# PhaseDriver.net
KiCad netlist of a schematic drawn in Altium Designer
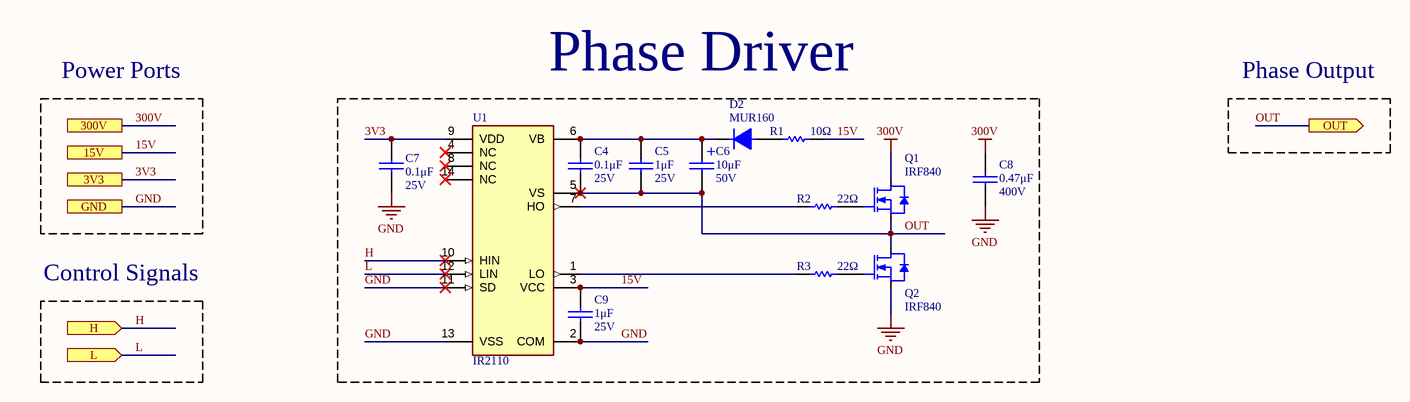
[diagram p0: PhaseDriver.SchDoc]

(export (version "E")
  (design (tool "Eeschema 10.0.6"))
  (components
    (comp (ref "C4")
      (value "0.1μF")
      (footprint "0805")
      (description "CAPACITOR")
      (fields (field (name "VOLTAGE RATING") "25V") (field (name "Comment") "CAP"))
      (libsource (lib "Inverter") (part "CAPACITOR"))
    )
    (comp (ref "C5")
      (value "1μF")
      (footprint "CAP100")
      (description "CAPACITOR")
      (fields (field (name "VOLTAGE RATING") "25V") (field (name "Comment") "CAP"))
      (libsource (lib "Inverter") (part "CAPACITOR"))
    )
    (comp (ref "C6")
      (value "10μF")
      (footprint "CAP100RP")
      (description "CAPACITOR POLARIZADO")
      (fields (field (name "VOLTAGE RATING") "50V") (field (name "Comment") "CAPPOL"))
      (libsource (lib "Inverter") (part "CAPACITOR POLARIZADO"))
    )
    (comp (ref "C7")
      (value "0.1μF")
      (footprint "0805")
      (description "CAPACITOR")
      (fields (field (name "VOLTAGE RATING") "25V") (field (name "Comment") "CAP"))
      (libsource (lib "Inverter") (part "CAPACITOR"))
    )
    (comp (ref "C8")
      (value "0.47μF")
      (footprint "CAP600")
      (description "CAPACITOR")
      (fields (field (name "VOLTAGE RATING") "400V") (field (name "Comment") "CAP"))
      (libsource (lib "Inverter") (part "CAPACITOR"))
    )
    (comp (ref "C9")
      (value "1μF")
      (footprint "CAP100")
      (description "CAPACITOR")
      (fields (field (name "VOLTAGE RATING") "25V") (field (name "Comment") "CAP"))
      (libsource (lib "Inverter") (part "CAPACITOR"))
    )
    (comp (ref "D2")
      (value "MUR160")
      (footprint "DO41")
      (fields (field (name "MANUFACTURER PART NUMBER") "MUR160"))
      (libsource (lib "Inverter") (part "MUR160"))
    )
    (comp (ref "Q1")
      (value "IRF840")
      (footprint "TO-220 V")
      (fields (field (name "MANUFACTURER") "Vishay") (field (name "MANUFACTURER PART NUMBER") "IRF840"))
      (libsource (lib "Inverter") (part "IRF840"))
    )
    (comp (ref "Q2")
      (value "IRF840")
      (footprint "TO-220 V")
      (fields (field (name "MANUFACTURER") "Vishay") (field (name "MANUFACTURER PART NUMBER") "IRF840"))
      (libsource (lib "Inverter") (part "IRF840"))
    )
    (comp (ref "R1")
      (value "10Ω")
      (footprint "0805")
      (description "RESISTOR")
      (fields (field (name "POWER") "1/10W") (field (name "Comment") "RES"))
      (libsource (lib "Inverter") (part "RESISTOR"))
    )
    (comp (ref "R2")
      (value "22Ω")
      (footprint "0805")
      (description "RESISTOR")
      (fields (field (name "POWER") "1/10W") (field (name "Comment") "RES"))
      (libsource (lib "Inverter") (part "RESISTOR"))
    )
    (comp (ref "R3")
      (value "22Ω")
      (footprint "0805")
      (description "RESISTOR")
      (fields (field (name "POWER") "1/10W") (field (name "Comment") "RES"))
      (libsource (lib "Inverter") (part "RESISTOR"))
    )
    (comp (ref "U1")
      (value "IR2110")
      (footprint "IR2110")
      (description "High and Low Side Driver")
      (fields
        (field (name "MANUFACTURER") "Infineon Technologies")
        (field (name "MANUFACTURER ORDER NUMBER") "IR2110")
      )
      (libsource (lib "Inverter") (part "IR2110"))
    )
  )
  (nets
    (net (code "1") (name "/3V3") (class "Default")
      (node (ref "C7") (pin "1") (pinfunction "1_1") (pintype "passive"))
      (node (ref "U1") (pin "9") (pinfunction "VDD_9") (pintype "power_in"))
    )
    (net (code "2") (name "/15V") (class "Default")
      (node (ref "C9") (pin "1") (pinfunction "1_1") (pintype "passive"))
      (node (ref "R1") (pin "1") (pinfunction "1_1") (pintype "passive"))
      (node (ref "U1") (pin "3") (pinfunction "VCC_3") (pintype "power_in"))
    )
    (net (code "3") (name "/H") (class "Default")
      (node (ref "U1") (pin "10") (pinfunction "HIN_10") (pintype "input+no_connect"))
    )
    (net (code "4") (name "/L") (class "Default")
      (node (ref "U1") (pin "12") (pinfunction "LIN_12") (pintype "input+no_connect"))
    )
    (net (code "5") (name "/OUT") (class "Default")
      (node (ref "C4") (pin "2") (pinfunction "2_2") (pintype "passive"))
      (node (ref "C5") (pin "2") (pinfunction "2_2") (pintype "passive"))
      (node (ref "C6") (pin "2") (pinfunction "2_2") (pintype "passive"))
      (node (ref "Q1") (pin "3") (pinfunction "S_3") (pintype "passive"))
      (node (ref "Q2") (pin "2") (pinfunction "D_2") (pintype "passive"))
      (node (ref "U1") (pin "5") (pinfunction "VS_5") (pintype "power_in"))
    )
    (net (code "6") (name "300V") (class "Default")
      (node (ref "C8") (pin "1") (pinfunction "1_1") (pintype "passive"))
      (node (ref "Q1") (pin "2") (pinfunction "D_2") (pintype "passive"))
    )
    (net (code "7") (name "GND") (class "Default")
      (node (ref "C7") (pin "2") (pinfunction "2_2") (pintype "passive"))
      (node (ref "C8") (pin "2") (pinfunction "2_2") (pintype "passive"))
      (node (ref "C9") (pin "2") (pinfunction "2_2") (pintype "passive"))
      (node (ref "Q2") (pin "3") (pinfunction "S_3") (pintype "passive"))
      (node (ref "U1") (pin "11") (pinfunction "SD_11") (pintype "input"))
      (node (ref "U1") (pin "13") (pinfunction "VSS_13") (pintype "power_in"))
      (node (ref "U1") (pin "2") (pinfunction "COM_2") (pintype "power_in"))
    )
    (net (code "8") (name "Net-(D2-Pad1)") (class "Default")
      (node (ref "D2") (pin "1") (pinfunction "1_1") (pintype "passive"))
      (node (ref "R1") (pin "2") (pinfunction "2_2") (pintype "passive"))
    )
    (net (code "9") (name "Net-(Q1-G)") (class "Default")
      (node (ref "Q1") (pin "1") (pinfunction "G_1") (pintype "passive"))
      (node (ref "R2") (pin "1") (pinfunction "1_1") (pintype "passive"))
    )
    (net (code "10") (name "Net-(Q2-G)") (class "Default")
      (node (ref "Q2") (pin "1") (pinfunction "G_1") (pintype "passive"))
      (node (ref "R3") (pin "1") (pinfunction "1_1") (pintype "passive"))
    )
    (net (code "11") (name "Net-(U1-HO)") (class "Default")
      (node (ref "R2") (pin "2") (pinfunction "2_2") (pintype "passive"))
      (node (ref "U1") (pin "7") (pinfunction "HO_7") (pintype "output"))
    )
    (net (code "12") (name "Net-(U1-LO)") (class "Default")
      (node (ref "R3") (pin "2") (pinfunction "2_2") (pintype "passive"))
      (node (ref "U1") (pin "1") (pinfunction "LO_1") (pintype "output"))
    )
    (net (code "13") (name "Net-(U1-VB)") (class "Default")
      (node (ref "C4") (pin "1") (pinfunction "1_1") (pintype "passive"))
      (node (ref "C5") (pin "1") (pinfunction "1_1") (pintype "passive"))
      (node (ref "C6") (pin "1") (pinfunction "1_1") (pintype "passive"))
      (node (ref "D2") (pin "2") (pinfunction "2_2") (pintype "passive"))
      (node (ref "U1") (pin "6") (pinfunction "VB_6") (pintype "power_in"))
    )
    (net (code "14") (name "unconnected-(U1-NC-Pad4)") (class "Default")
      (node (ref "U1") (pin "4") (pinfunction "NC_4") (pintype "passive+no_connect"))
    )
    (net (code "15") (name "unconnected-(U1-NC-Pad8)") (class "Default")
      (node (ref "U1") (pin "8") (pinfunction "NC_8") (pintype "passive+no_connect"))
    )
    (net (code "16") (name "unconnected-(U1-NC-Pad14)") (class "Default")
      (node (ref "U1") (pin "14") (pinfunction "NC_14") (pintype "passive+no_connect"))
    )
  )
)
